# CORE.net
KiCad netlist of a schematic drawn in Altium Designer
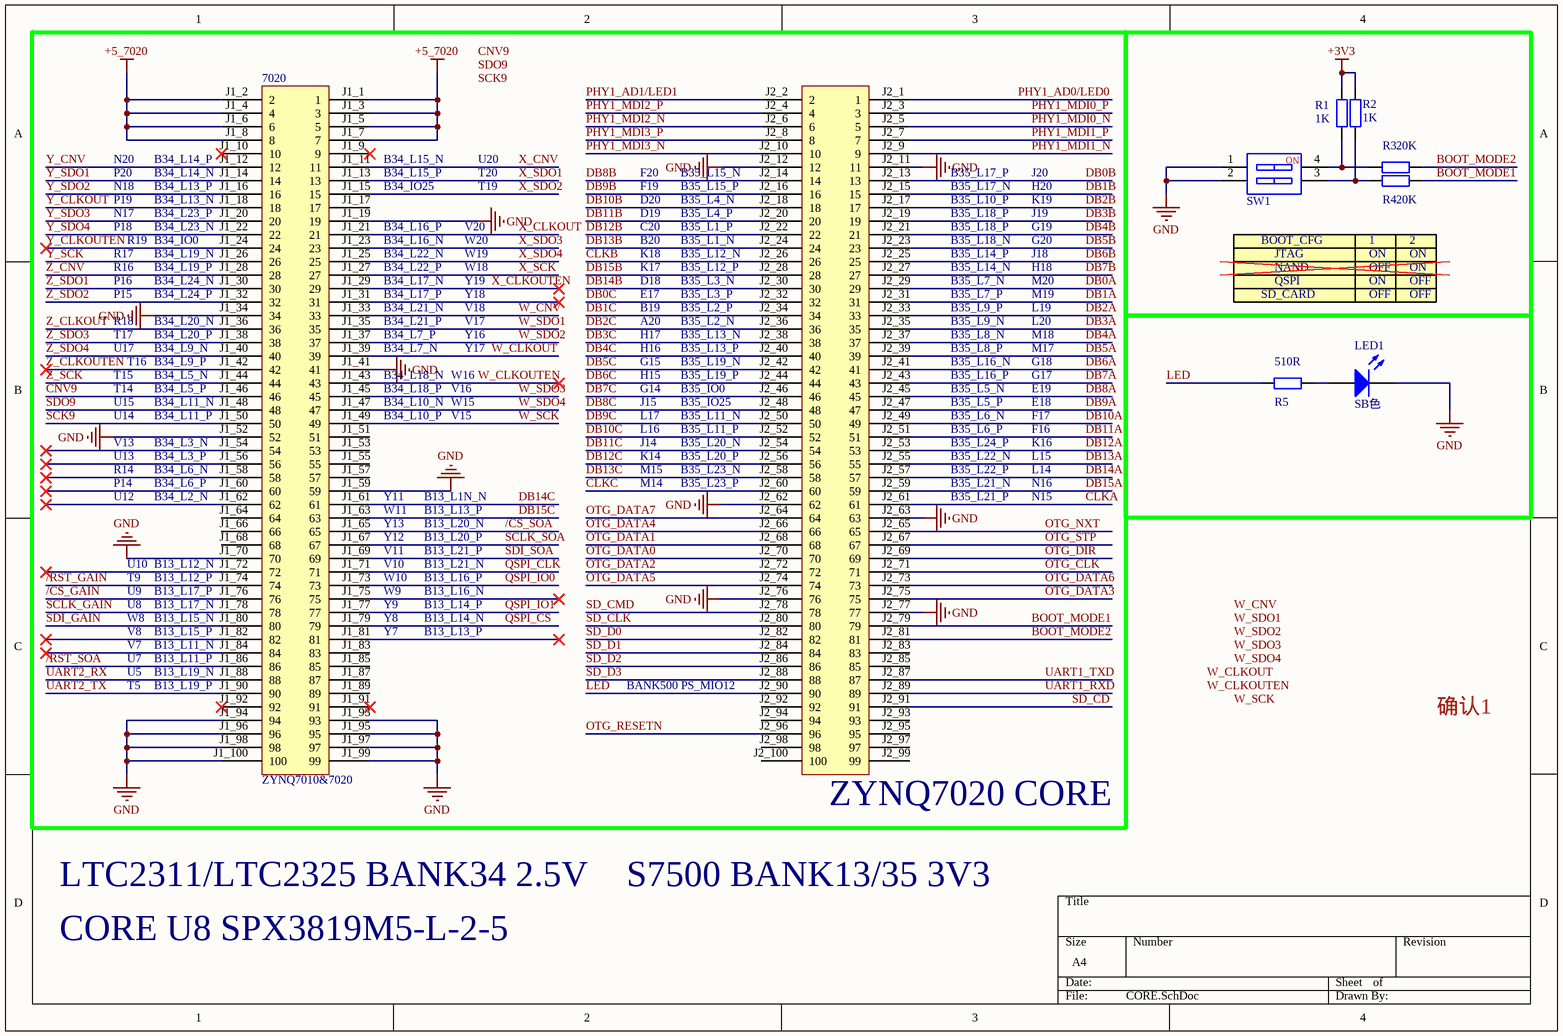
[diagram p0: CORE.SchDoc]

(export (version "E")
  (design (tool "Eeschema 10.0.6"))
  (components
    (comp (ref "7020")
      (value "ZYNQ7010&7020")
      (footprint "ZYNQ7010&7020_CB")
      (description "ZYNQ7010&7020 Core Board")
      (libsource (lib "领航者ZYNQ底板SCH&PCB封装库") (part "ZYNQ7010&7020"))
    )
    (comp (ref "LED1")
      (value "SB色")
      (footprint "LED0603_B")
      (description "贴片LED")
      (libsource (lib "0.3 - LED发光二极管-IR二极管_接收管-光耦") (part "LED"))
    )
    (comp (ref "R1")
      (value "1K")
      (footprint "R0402_L")
      (description "贴片电阻")
      (libsource (lib "0.1 - 电阻-电容-电感-保险丝-晶振-晶体-磁珠-电位器-法拉电容-馈通电容") (part "R"))
    )
    (comp (ref "R2")
      (value "1K")
      (footprint "R0402_L")
      (description "贴片电阻")
      (libsource (lib "0.1 - 电阻-电容-电感-保险丝-晶振-晶体-磁珠-电位器-法拉电容-馈通电容") (part "R"))
    )
    (comp (ref "R3")
      (value "20K")
      (footprint "R0402_L")
      (description "贴片电阻")
      (libsource (lib "0.1 - 电阻-电容-电感-保险丝-晶振-晶体-磁珠-电位器-法拉电容-馈通电容") (part "R"))
    )
    (comp (ref "R4")
      (value "20K")
      (footprint "R0402_L")
      (description "贴片电阻")
      (libsource (lib "0.1 - 电阻-电容-电感-保险丝-晶振-晶体-磁珠-电位器-法拉电容-馈通电容") (part "R"))
    )
    (comp (ref "R5")
      (value "510R")
      (footprint "R0603_L")
      (description "贴片电阻")
      (libsource (lib "0.1 - 电阻-电容-电感-保险丝-晶振-晶体-磁珠-电位器-法拉电容-馈通电容") (part "R"))
    )
    (comp (ref "SW1")
      (value "DIP-SW-2P")
      (footprint "SW DIP-2P")
      (description "2路拨码开关")
      (libsource (lib "0.5 - 按键_开关_蜂鸣器_电池_测试点_Mark点_铜柱") (part "DIP-SW-2P"))
    )
  )
  (nets
    (net (code "1") (name "+3V3") (class "Default")
      (node (ref "R1") (pin "2") (pinfunction "2_2") (pintype "passive"))
      (node (ref "R2") (pin "2") (pinfunction "2_2") (pintype "passive"))
    )
    (net (code "2") (name "+5_7020") (class "Default")
      (node (ref "7020") (pin "J1_1") (pinfunction "1_J1_1") (pintype "passive"))
      (node (ref "7020") (pin "J1_2") (pinfunction "2_J1_2") (pintype "passive"))
      (node (ref "7020") (pin "J1_3") (pinfunction "3_J1_3") (pintype "passive"))
      (node (ref "7020") (pin "J1_4") (pinfunction "4_J1_4") (pintype "passive"))
      (node (ref "7020") (pin "J1_5") (pinfunction "5_J1_5") (pintype "passive"))
      (node (ref "7020") (pin "J1_6") (pinfunction "6_J1_6") (pintype "passive"))
      (node (ref "7020") (pin "J1_7") (pinfunction "7_J1_7") (pintype "passive"))
      (node (ref "7020") (pin "J1_8") (pinfunction "8_J1_8") (pintype "passive"))
    )
    (net (code "3") (name "/BOOT_MODE1") (class "Default")
      (node (ref "7020") (pin "J2_79") (pinfunction "79_J2_79") (pintype "passive"))
      (node (ref "R4") (pin "2") (pinfunction "2_2") (pintype "passive"))
    )
    (net (code "4") (name "/BOOT_MODE2") (class "Default")
      (node (ref "7020") (pin "J2_81") (pinfunction "81_J2_81") (pintype "passive"))
      (node (ref "R3") (pin "2") (pinfunction "2_2") (pintype "passive"))
    )
    (net (code "5") (name "/CLKA") (class "Default")
      (node (ref "7020") (pin "J2_61") (pinfunction "61_J2_61") (pintype "passive"))
    )
    (net (code "6") (name "/CLKB") (class "Default")
      (node (ref "7020") (pin "J2_26") (pinfunction "26_J2_26") (pintype "passive"))
    )
    (net (code "7") (name "/CLKC") (class "Default")
      (node (ref "7020") (pin "J2_60") (pinfunction "60_J2_60") (pintype "passive"))
    )
    (net (code "8") (name "/CNV9") (class "Default")
      (node (ref "7020") (pin "J1_46") (pinfunction "46_J1_46") (pintype "passive"))
    )
    (net (code "9") (name "/DB0A") (class "Default")
      (node (ref "7020") (pin "J2_29") (pinfunction "29_J2_29") (pintype "passive"))
    )
    (net (code "10") (name "/DB0B") (class "Default")
      (node (ref "7020") (pin "J2_13") (pinfunction "13_J2_13") (pintype "passive"))
    )
    (net (code "11") (name "/DB0C") (class "Default")
      (node (ref "7020") (pin "J2_32") (pinfunction "32_J2_32") (pintype "passive"))
    )
    (net (code "12") (name "/DB1A") (class "Default")
      (node (ref "7020") (pin "J2_31") (pinfunction "31_J2_31") (pintype "passive"))
    )
    (net (code "13") (name "/DB1B") (class "Default")
      (node (ref "7020") (pin "J2_15") (pinfunction "15_J2_15") (pintype "passive"))
    )
    (net (code "14") (name "/DB1C") (class "Default")
      (node (ref "7020") (pin "J2_34") (pinfunction "34_J2_34") (pintype "passive"))
    )
    (net (code "15") (name "/DB2A") (class "Default")
      (node (ref "7020") (pin "J2_33") (pinfunction "33_J2_33") (pintype "passive"))
    )
    (net (code "16") (name "/DB2B") (class "Default")
      (node (ref "7020") (pin "J2_17") (pinfunction "17_J2_17") (pintype "passive"))
    )
    (net (code "17") (name "/DB2C") (class "Default")
      (node (ref "7020") (pin "J2_36") (pinfunction "36_J2_36") (pintype "passive"))
    )
    (net (code "18") (name "/DB3A") (class "Default")
      (node (ref "7020") (pin "J2_35") (pinfunction "35_J2_35") (pintype "passive"))
    )
    (net (code "19") (name "/DB3B") (class "Default")
      (node (ref "7020") (pin "J2_19") (pinfunction "19_J2_19") (pintype "passive"))
    )
    (net (code "20") (name "/DB3C") (class "Default")
      (node (ref "7020") (pin "J2_38") (pinfunction "38_J2_38") (pintype "passive"))
    )
    (net (code "21") (name "/DB4A") (class "Default")
      (node (ref "7020") (pin "J2_37") (pinfunction "37_J2_37") (pintype "passive"))
    )
    (net (code "22") (name "/DB4B") (class "Default")
      (node (ref "7020") (pin "J2_21") (pinfunction "21_J2_21") (pintype "passive"))
    )
    (net (code "23") (name "/DB4C") (class "Default")
      (node (ref "7020") (pin "J2_40") (pinfunction "40_J2_40") (pintype "passive"))
    )
    (net (code "24") (name "/DB5A") (class "Default")
      (node (ref "7020") (pin "J2_39") (pinfunction "39_J2_39") (pintype "passive"))
    )
    (net (code "25") (name "/DB5B") (class "Default")
      (node (ref "7020") (pin "J2_23") (pinfunction "23_J2_23") (pintype "passive"))
    )
    (net (code "26") (name "/DB5C") (class "Default")
      (node (ref "7020") (pin "J2_42") (pinfunction "42_J2_42") (pintype "passive"))
    )
    (net (code "27") (name "/DB6A") (class "Default")
      (node (ref "7020") (pin "J2_41") (pinfunction "41_J2_41") (pintype "passive"))
    )
    (net (code "28") (name "/DB6B") (class "Default")
      (node (ref "7020") (pin "J2_25") (pinfunction "25_J2_25") (pintype "passive"))
    )
    (net (code "29") (name "/DB6C") (class "Default")
      (node (ref "7020") (pin "J2_44") (pinfunction "44_J2_44") (pintype "passive"))
    )
    (net (code "30") (name "/DB7A") (class "Default")
      (node (ref "7020") (pin "J2_43") (pinfunction "43_J2_43") (pintype "passive"))
    )
    (net (code "31") (name "/DB7B") (class "Default")
      (node (ref "7020") (pin "J2_27") (pinfunction "27_J2_27") (pintype "passive"))
    )
    (net (code "32") (name "/DB7C") (class "Default")
      (node (ref "7020") (pin "J2_46") (pinfunction "46_J2_46") (pintype "passive"))
    )
    (net (code "33") (name "/DB8A") (class "Default")
      (node (ref "7020") (pin "J2_45") (pinfunction "45_J2_45") (pintype "passive"))
    )
    (net (code "34") (name "/DB8B") (class "Default")
      (node (ref "7020") (pin "J2_14") (pinfunction "14_J2_14") (pintype "passive"))
    )
    (net (code "35") (name "/DB8C") (class "Default")
      (node (ref "7020") (pin "J2_48") (pinfunction "48_J2_48") (pintype "passive"))
    )
    (net (code "36") (name "/DB9A") (class "Default")
      (node (ref "7020") (pin "J2_47") (pinfunction "47_J2_47") (pintype "passive"))
    )
    (net (code "37") (name "/DB9B") (class "Default")
      (node (ref "7020") (pin "J2_16") (pinfunction "16_J2_16") (pintype "passive"))
    )
    (net (code "38") (name "/DB9C") (class "Default")
      (node (ref "7020") (pin "J2_50") (pinfunction "50_J2_50") (pintype "passive"))
    )
    (net (code "39") (name "/DB10A") (class "Default")
      (node (ref "7020") (pin "J2_49") (pinfunction "49_J2_49") (pintype "passive"))
    )
    (net (code "40") (name "/DB10B") (class "Default")
      (node (ref "7020") (pin "J2_18") (pinfunction "18_J2_18") (pintype "passive"))
    )
    (net (code "41") (name "/DB10C") (class "Default")
      (node (ref "7020") (pin "J2_52") (pinfunction "52_J2_52") (pintype "passive"))
    )
    (net (code "42") (name "/DB11A") (class "Default")
      (node (ref "7020") (pin "J2_51") (pinfunction "51_J2_51") (pintype "passive"))
    )
    (net (code "43") (name "/DB11B") (class "Default")
      (node (ref "7020") (pin "J2_20") (pinfunction "20_J2_20") (pintype "passive"))
    )
    (net (code "44") (name "/DB11C") (class "Default")
      (node (ref "7020") (pin "J2_54") (pinfunction "54_J2_54") (pintype "passive"))
    )
    (net (code "45") (name "/DB12A") (class "Default")
      (node (ref "7020") (pin "J2_53") (pinfunction "53_J2_53") (pintype "passive"))
    )
    (net (code "46") (name "/DB12B") (class "Default")
      (node (ref "7020") (pin "J2_22") (pinfunction "22_J2_22") (pintype "passive"))
    )
    (net (code "47") (name "/DB12C") (class "Default")
      (node (ref "7020") (pin "J2_56") (pinfunction "56_J2_56") (pintype "passive"))
    )
    (net (code "48") (name "/DB13A") (class "Default")
      (node (ref "7020") (pin "J2_55") (pinfunction "55_J2_55") (pintype "passive"))
    )
    (net (code "49") (name "/DB13B") (class "Default")
      (node (ref "7020") (pin "J2_24") (pinfunction "24_J2_24") (pintype "passive"))
    )
    (net (code "50") (name "/DB13C") (class "Default")
      (node (ref "7020") (pin "J2_58") (pinfunction "58_J2_58") (pintype "passive"))
    )
    (net (code "51") (name "/DB14A") (class "Default")
      (node (ref "7020") (pin "J2_57") (pinfunction "57_J2_57") (pintype "passive"))
    )
    (net (code "52") (name "/DB14B") (class "Default")
      (node (ref "7020") (pin "J2_30") (pinfunction "30_J2_30") (pintype "passive"))
    )
    (net (code "53") (name "/DB14C") (class "Default")
      (node (ref "7020") (pin "J1_61") (pinfunction "61_J1_61") (pintype "passive"))
    )
    (net (code "54") (name "/DB15A") (class "Default")
      (node (ref "7020") (pin "J2_59") (pinfunction "59_J2_59") (pintype "passive"))
    )
    (net (code "55") (name "/DB15B") (class "Default")
      (node (ref "7020") (pin "J2_28") (pinfunction "28_J2_28") (pintype "passive"))
    )
    (net (code "56") (name "/DB15C") (class "Default")
      (node (ref "7020") (pin "J1_63") (pinfunction "63_J1_63") (pintype "passive"))
    )
    (net (code "57") (name "/LED") (class "Default")
      (node (ref "7020") (pin "J2_90") (pinfunction "90_J2_90") (pintype "passive"))
      (node (ref "R5") (pin "1") (pinfunction "1_1") (pintype "passive"))
    )
    (net (code "58") (name "/OTG_CLK") (class "Default")
      (node (ref "7020") (pin "J2_71") (pinfunction "71_J2_71") (pintype "passive"))
    )
    (net (code "59") (name "/OTG_DATA0") (class "Default")
      (node (ref "7020") (pin "J2_70") (pinfunction "70_J2_70") (pintype "passive"))
    )
    (net (code "60") (name "/OTG_DATA1") (class "Default")
      (node (ref "7020") (pin "J2_68") (pinfunction "68_J2_68") (pintype "passive"))
    )
    (net (code "61") (name "/OTG_DATA2") (class "Default")
      (node (ref "7020") (pin "J2_72") (pinfunction "72_J2_72") (pintype "passive"))
    )
    (net (code "62") (name "/OTG_DATA3") (class "Default")
      (node (ref "7020") (pin "J2_75") (pinfunction "75_J2_75") (pintype "passive"))
    )
    (net (code "63") (name "/OTG_DATA4") (class "Default")
      (node (ref "7020") (pin "J2_66") (pinfunction "66_J2_66") (pintype "passive"))
    )
    (net (code "64") (name "/OTG_DATA5") (class "Default")
      (node (ref "7020") (pin "J2_74") (pinfunction "74_J2_74") (pintype "passive"))
    )
    (net (code "65") (name "/OTG_DATA6") (class "Default")
      (node (ref "7020") (pin "J2_73") (pinfunction "73_J2_73") (pintype "passive"))
    )
    (net (code "66") (name "/OTG_DATA7") (class "Default")
      (node (ref "7020") (pin "J2_64") (pinfunction "64_J2_64") (pintype "passive"))
    )
    (net (code "67") (name "/OTG_DIR") (class "Default")
      (node (ref "7020") (pin "J2_69") (pinfunction "69_J2_69") (pintype "passive"))
    )
    (net (code "68") (name "/OTG_NXT") (class "Default")
      (node (ref "7020") (pin "J2_65") (pinfunction "65_J2_65") (pintype "passive"))
    )
    (net (code "69") (name "/OTG_RESETN") (class "Default")
      (node (ref "7020") (pin "J2_96") (pinfunction "96_J2_96") (pintype "passive"))
    )
    (net (code "70") (name "/OTG_STP") (class "Default")
      (node (ref "7020") (pin "J2_67") (pinfunction "67_J2_67") (pintype "passive"))
    )
    (net (code "71") (name "/PHY1_AD0{slash}LED0") (class "Default")
      (node (ref "7020") (pin "J2_1") (pinfunction "1_J2_1") (pintype "passive"))
    )
    (net (code "72") (name "/PHY1_AD1{slash}LED1") (class "Default")
      (node (ref "7020") (pin "J2_2") (pinfunction "2_J2_2") (pintype "passive"))
    )
    (net (code "73") (name "/PHY1_MDI0_N") (class "Default")
      (node (ref "7020") (pin "J2_5") (pinfunction "5_J2_5") (pintype "passive"))
    )
    (net (code "74") (name "/PHY1_MDI0_P") (class "Default")
      (node (ref "7020") (pin "J2_3") (pinfunction "3_J2_3") (pintype "passive"))
    )
    (net (code "75") (name "/PHY1_MDI1_N") (class "Default")
      (node (ref "7020") (pin "J2_9") (pinfunction "9_J2_9") (pintype "passive"))
    )
    (net (code "76") (name "/PHY1_MDI1_P") (class "Default")
      (node (ref "7020") (pin "J2_7") (pinfunction "7_J2_7") (pintype "passive"))
    )
    (net (code "77") (name "/PHY1_MDI2_N") (class "Default")
      (node (ref "7020") (pin "J2_6") (pinfunction "6_J2_6") (pintype "passive"))
    )
    (net (code "78") (name "/PHY1_MDI2_P") (class "Default")
      (node (ref "7020") (pin "J2_4") (pinfunction "4_J2_4") (pintype "passive"))
    )
    (net (code "79") (name "/PHY1_MDI3_N") (class "Default")
      (node (ref "7020") (pin "J2_10") (pinfunction "10_J2_10") (pintype "passive"))
    )
    (net (code "80") (name "/PHY1_MDI3_P") (class "Default")
      (node (ref "7020") (pin "J2_8") (pinfunction "8_J2_8") (pintype "passive"))
    )
    (net (code "81") (name "/QSPI_CLK") (class "Default")
      (node (ref "7020") (pin "J1_71") (pinfunction "71_J1_71") (pintype "passive"))
    )
    (net (code "82") (name "/QSPI_CS") (class "Default")
      (node (ref "7020") (pin "J1_79") (pinfunction "79_J1_79") (pintype "passive"))
    )
    (net (code "83") (name "/QSPI_IO0") (class "Default")
      (node (ref "7020") (pin "J1_73") (pinfunction "73_J1_73") (pintype "passive"))
    )
    (net (code "84") (name "/QSPI_IO1") (class "Default")
      (node (ref "7020") (pin "J1_77") (pinfunction "77_J1_77") (pintype "passive"))
    )
    (net (code "85") (name "/SCK9") (class "Default")
      (node (ref "7020") (pin "J1_50") (pinfunction "50_J1_50") (pintype "passive"))
    )
    (net (code "86") (name "/SCLK_GAIN") (class "Default")
      (node (ref "7020") (pin "J1_78") (pinfunction "78_J1_78") (pintype "passive"))
    )
    (net (code "87") (name "/SCLK_SOA") (class "Default")
      (node (ref "7020") (pin "J1_67") (pinfunction "67_J1_67") (pintype "passive"))
    )
    (net (code "88") (name "/SDI_GAIN") (class "Default")
      (node (ref "7020") (pin "J1_80") (pinfunction "80_J1_80") (pintype "passive"))
    )
    (net (code "89") (name "/SDI_SOA") (class "Default")
      (node (ref "7020") (pin "J1_69") (pinfunction "69_J1_69") (pintype "passive"))
    )
    (net (code "90") (name "/SDO9") (class "Default")
      (node (ref "7020") (pin "J1_48") (pinfunction "48_J1_48") (pintype "passive"))
    )
    (net (code "91") (name "/SD_CD") (class "Default")
      (node (ref "7020") (pin "J2_91") (pinfunction "91_J2_91") (pintype "passive"))
    )
    (net (code "92") (name "/SD_CLK") (class "Default")
      (node (ref "7020") (pin "J2_80") (pinfunction "80_J2_80") (pintype "passive"))
    )
    (net (code "93") (name "/SD_CMD") (class "Default")
      (node (ref "7020") (pin "J2_78") (pinfunction "78_J2_78") (pintype "passive"))
    )
    (net (code "94") (name "/SD_D0") (class "Default")
      (node (ref "7020") (pin "J2_82") (pinfunction "82_J2_82") (pintype "passive"))
    )
    (net (code "95") (name "/SD_D1") (class "Default")
      (node (ref "7020") (pin "J2_84") (pinfunction "84_J2_84") (pintype "passive"))
    )
    (net (code "96") (name "/SD_D2") (class "Default")
      (node (ref "7020") (pin "J2_86") (pinfunction "86_J2_86") (pintype "passive"))
    )
    (net (code "97") (name "/SD_D3") (class "Default")
      (node (ref "7020") (pin "J2_88") (pinfunction "88_J2_88") (pintype "passive"))
    )
    (net (code "98") (name "/UART1_RXD") (class "Default")
      (node (ref "7020") (pin "J2_89") (pinfunction "89_J2_89") (pintype "passive"))
    )
    (net (code "99") (name "/UART1_TXD") (class "Default")
      (node (ref "7020") (pin "J2_87") (pinfunction "87_J2_87") (pintype "passive"))
    )
    (net (code "100") (name "/UART2_RX") (class "Default")
      (node (ref "7020") (pin "J1_88") (pinfunction "88_J1_88") (pintype "passive"))
    )
    (net (code "101") (name "/UART2_TX") (class "Default")
      (node (ref "7020") (pin "J1_90") (pinfunction "90_J1_90") (pintype "passive"))
    )
    (net (code "102") (name "/W_CLKOUT") (class "Default")
      (node (ref "7020") (pin "J1_39") (pinfunction "39_J1_39") (pintype "passive"))
    )
    (net (code "103") (name "/W_CLKOUTEN") (class "Default")
      (node (ref "7020") (pin "J1_43") (pinfunction "43_J1_43") (pintype "passive+no_connect"))
    )
    (net (code "104") (name "/W_CNV") (class "Default")
      (node (ref "7020") (pin "J1_33") (pinfunction "33_J1_33") (pintype "passive"))
    )
    (net (code "105") (name "/W_SCK") (class "Default")
      (node (ref "7020") (pin "J1_49") (pinfunction "49_J1_49") (pintype "passive"))
    )
    (net (code "106") (name "/W_SDO1") (class "Default")
      (node (ref "7020") (pin "J1_35") (pinfunction "35_J1_35") (pintype "passive"))
    )
    (net (code "107") (name "/W_SDO2") (class "Default")
      (node (ref "7020") (pin "J1_37") (pinfunction "37_J1_37") (pintype "passive"))
    )
    (net (code "108") (name "/W_SDO3") (class "Default")
      (node (ref "7020") (pin "J1_45") (pinfunction "45_J1_45") (pintype "passive"))
    )
    (net (code "109") (name "/W_SDO4") (class "Default")
      (node (ref "7020") (pin "J1_47") (pinfunction "47_J1_47") (pintype "passive"))
    )
    (net (code "110") (name "/X_CLKOUT") (class "Default")
      (node (ref "7020") (pin "J1_21") (pinfunction "21_J1_21") (pintype "passive"))
    )
    (net (code "111") (name "/X_CLKOUTEN") (class "Default")
      (node (ref "7020") (pin "J1_29") (pinfunction "29_J1_29") (pintype "passive+no_connect"))
    )
    (net (code "112") (name "/X_CNV") (class "Default")
      (node (ref "7020") (pin "J1_11") (pinfunction "11_J1_11") (pintype "passive"))
    )
    (net (code "113") (name "/X_SCK") (class "Default")
      (node (ref "7020") (pin "J1_27") (pinfunction "27_J1_27") (pintype "passive"))
    )
    (net (code "114") (name "/X_SDO1") (class "Default")
      (node (ref "7020") (pin "J1_13") (pinfunction "13_J1_13") (pintype "passive"))
    )
    (net (code "115") (name "/X_SDO2") (class "Default")
      (node (ref "7020") (pin "J1_15") (pinfunction "15_J1_15") (pintype "passive"))
    )
    (net (code "116") (name "/X_SDO3") (class "Default")
      (node (ref "7020") (pin "J1_23") (pinfunction "23_J1_23") (pintype "passive"))
    )
    (net (code "117") (name "/X_SDO4") (class "Default")
      (node (ref "7020") (pin "J1_25") (pinfunction "25_J1_25") (pintype "passive"))
    )
    (net (code "118") (name "/Y_CLKOUT") (class "Default")
      (node (ref "7020") (pin "J1_18") (pinfunction "18_J1_18") (pintype "passive"))
    )
    (net (code "119") (name "/Y_CLKOUTEN") (class "Default")
      (node (ref "7020") (pin "J1_24") (pinfunction "24_J1_24") (pintype "passive+no_connect"))
    )
    (net (code "120") (name "/Y_CNV") (class "Default")
      (node (ref "7020") (pin "J1_12") (pinfunction "12_J1_12") (pintype "passive"))
    )
    (net (code "121") (name "/Y_SCK") (class "Default")
      (node (ref "7020") (pin "J1_26") (pinfunction "26_J1_26") (pintype "passive"))
    )
    (net (code "122") (name "/Y_SDO1") (class "Default")
      (node (ref "7020") (pin "J1_14") (pinfunction "14_J1_14") (pintype "passive"))
    )
    (net (code "123") (name "/Y_SDO2") (class "Default")
      (node (ref "7020") (pin "J1_16") (pinfunction "16_J1_16") (pintype "passive"))
    )
    (net (code "124") (name "/Y_SDO3") (class "Default")
      (node (ref "7020") (pin "J1_20") (pinfunction "20_J1_20") (pintype "passive"))
    )
    (net (code "125") (name "/Y_SDO4") (class "Default")
      (node (ref "7020") (pin "J1_22") (pinfunction "22_J1_22") (pintype "passive"))
    )
    (net (code "126") (name "/Z_CLKOUT") (class "Default")
      (node (ref "7020") (pin "J1_36") (pinfunction "36_J1_36") (pintype "passive"))
    )
    (net (code "127") (name "/Z_CLKOUTEN") (class "Default")
      (node (ref "7020") (pin "J1_42") (pinfunction "42_J1_42") (pintype "passive+no_connect"))
    )
    (net (code "128") (name "/Z_CNV") (class "Default")
      (node (ref "7020") (pin "J1_28") (pinfunction "28_J1_28") (pintype "passive"))
    )
    (net (code "129") (name "/Z_SCK") (class "Default")
      (node (ref "7020") (pin "J1_44") (pinfunction "44_J1_44") (pintype "passive"))
    )
    (net (code "130") (name "/Z_SDO1") (class "Default")
      (node (ref "7020") (pin "J1_30") (pinfunction "30_J1_30") (pintype "passive"))
    )
    (net (code "131") (name "/Z_SDO2") (class "Default")
      (node (ref "7020") (pin "J1_32") (pinfunction "32_J1_32") (pintype "passive"))
    )
    (net (code "132") (name "/Z_SDO3") (class "Default")
      (node (ref "7020") (pin "J1_38") (pinfunction "38_J1_38") (pintype "passive"))
    )
    (net (code "133") (name "/Z_SDO4") (class "Default")
      (node (ref "7020") (pin "J1_40") (pinfunction "40_J1_40") (pintype "passive"))
    )
    (net (code "134") (name "/{slash}CS_GAIN") (class "Default")
      (node (ref "7020") (pin "J1_76") (pinfunction "76_J1_76") (pintype "passive"))
    )
    (net (code "135") (name "/{slash}CS_SOA") (class "Default")
      (node (ref "7020") (pin "J1_65") (pinfunction "65_J1_65") (pintype "passive"))
    )
    (net (code "136") (name "/{slash}RST_GAIN") (class "Default")
      (node (ref "7020") (pin "J1_74") (pinfunction "74_J1_74") (pintype "passive"))
    )
    (net (code "137") (name "/{slash}RST_SOA") (class "Default")
      (node (ref "7020") (pin "J1_86") (pinfunction "86_J1_86") (pintype "passive"))
    )
    (net (code "138") (name "GND") (class "Default")
      (node (ref "7020") (pin "J1_100") (pinfunction "100_J1_100") (pintype "passive"))
      (node (ref "7020") (pin "J1_19") (pinfunction "19_J1_19") (pintype "passive"))
      (node (ref "7020") (pin "J1_34") (pinfunction "34_J1_34") (pintype "passive"))
      (node (ref "7020") (pin "J1_41") (pinfunction "41_J1_41") (pintype "passive"))
      (node (ref "7020") (pin "J1_52") (pinfunction "52_J1_52") (pintype "passive"))
      (node (ref "7020") (pin "J1_59") (pinfunction "59_J1_59") (pintype "passive"))
      (node (ref "7020") (pin "J1_70") (pinfunction "70_J1_70") (pintype "passive"))
      (node (ref "7020") (pin "J1_93") (pinfunction "93_J1_93") (pintype "passive"))
      (node (ref "7020") (pin "J1_94") (pinfunction "94_J1_94") (pintype "passive"))
      (node (ref "7020") (pin "J1_95") (pinfunction "95_J1_95") (pintype "passive"))
      (node (ref "7020") (pin "J1_96") (pinfunction "96_J1_96") (pintype "passive"))
      (node (ref "7020") (pin "J1_97") (pinfunction "97_J1_97") (pintype "passive"))
      (node (ref "7020") (pin "J1_98") (pinfunction "98_J1_98") (pintype "passive"))
      (node (ref "7020") (pin "J1_99") (pinfunction "99_J1_99") (pintype "passive"))
      (node (ref "7020") (pin "J2_11") (pinfunction "11_J2_11") (pintype "passive"))
      (node (ref "7020") (pin "J2_12") (pinfunction "12_J2_12") (pintype "passive"))
      (node (ref "7020") (pin "J2_62") (pinfunction "62_J2_62") (pintype "passive"))
      (node (ref "7020") (pin "J2_63") (pinfunction "63_J2_63") (pintype "passive"))
      (node (ref "7020") (pin "J2_76") (pinfunction "76_J2_76") (pintype "passive"))
      (node (ref "7020") (pin "J2_77") (pinfunction "77_J2_77") (pintype "passive"))
      (node (ref "LED1") (pin "2") (pinfunction "K_2") (pintype "passive"))
      (node (ref "SW1") (pin "1") (pinfunction "1_1") (pintype "passive"))
      (node (ref "SW1") (pin "2") (pinfunction "2_2") (pintype "passive"))
    )
    (net (code "139") (name "Net-(LED1-A)") (class "Default")
      (node (ref "LED1") (pin "1") (pinfunction "A_1") (pintype "passive"))
      (node (ref "R5") (pin "2") (pinfunction "2_2") (pintype "passive"))
    )
    (net (code "140") (name "Net-(R1-Pad1)") (class "Default")
      (node (ref "R1") (pin "1") (pinfunction "1_1") (pintype "passive"))
      (node (ref "R3") (pin "1") (pinfunction "1_1") (pintype "passive"))
      (node (ref "SW1") (pin "4") (pinfunction "4_4") (pintype "passive"))
    )
    (net (code "141") (name "Net-(R2-Pad1)") (class "Default")
      (node (ref "R2") (pin "1") (pinfunction "1_1") (pintype "passive"))
      (node (ref "R4") (pin "1") (pinfunction "1_1") (pintype "passive"))
      (node (ref "SW1") (pin "3") (pinfunction "3_3") (pintype "passive"))
    )
    (net (code "142") (name "unconnected-(7020-9-PadJ1_9)") (class "Default")
      (node (ref "7020") (pin "J1_9") (pinfunction "9_J1_9") (pintype "passive+no_connect"))
    )
    (net (code "143") (name "unconnected-(7020-10-PadJ1_10)") (class "Default")
      (node (ref "7020") (pin "J1_10") (pinfunction "10_J1_10") (pintype "passive+no_connect"))
    )
    (net (code "144") (name "unconnected-(7020-17-PadJ1_17)") (class "Default")
      (node (ref "7020") (pin "J1_17") (pinfunction "17_J1_17") (pintype "passive"))
    )
    (net (code "145") (name "unconnected-(7020-31-PadJ1_31)") (class "Default")
      (node (ref "7020") (pin "J1_31") (pinfunction "31_J1_31") (pintype "passive+no_connect"))
    )
    (net (code "146") (name "unconnected-(7020-51-PadJ1_51)") (class "Default")
      (node (ref "7020") (pin "J1_51") (pinfunction "51_J1_51") (pintype "passive"))
    )
    (net (code "147") (name "unconnected-(7020-53-PadJ1_53)") (class "Default")
      (node (ref "7020") (pin "J1_53") (pinfunction "53_J1_53") (pintype "passive"))
    )
    (net (code "148") (name "unconnected-(7020-54-PadJ1_54)") (class "Default")
      (node (ref "7020") (pin "J1_54") (pinfunction "54_J1_54") (pintype "passive+no_connect"))
    )
    (net (code "149") (name "unconnected-(7020-55-PadJ1_55)") (class "Default")
      (node (ref "7020") (pin "J1_55") (pinfunction "55_J1_55") (pintype "passive"))
    )
    (net (code "150") (name "unconnected-(7020-56-PadJ1_56)") (class "Default")
      (node (ref "7020") (pin "J1_56") (pinfunction "56_J1_56") (pintype "passive+no_connect"))
    )
    (net (code "151") (name "unconnected-(7020-57-PadJ1_57)") (class "Default")
      (node (ref "7020") (pin "J1_57") (pinfunction "57_J1_57") (pintype "passive"))
    )
    (net (code "152") (name "unconnected-(7020-58-PadJ1_58)") (class "Default")
      (node (ref "7020") (pin "J1_58") (pinfunction "58_J1_58") (pintype "passive+no_connect"))
    )
    (net (code "153") (name "unconnected-(7020-60-PadJ1_60)") (class "Default")
      (node (ref "7020") (pin "J1_60") (pinfunction "60_J1_60") (pintype "passive+no_connect"))
    )
    (net (code "154") (name "unconnected-(7020-62-PadJ1_62)") (class "Default")
      (node (ref "7020") (pin "J1_62") (pinfunction "62_J1_62") (pintype "passive+no_connect"))
    )
    (net (code "155") (name "unconnected-(7020-64-PadJ1_64)") (class "Default")
      (node (ref "7020") (pin "J1_64") (pinfunction "64_J1_64") (pintype "passive"))
    )
    (net (code "156") (name "unconnected-(7020-66-PadJ1_66)") (class "Default")
      (node (ref "7020") (pin "J1_66") (pinfunction "66_J1_66") (pintype "passive"))
    )
    (net (code "157") (name "unconnected-(7020-68-PadJ1_68)") (class "Default")
      (node (ref "7020") (pin "J1_68") (pinfunction "68_J1_68") (pintype "passive"))
    )
    (net (code "158") (name "unconnected-(7020-72-PadJ1_72)") (class "Default")
      (node (ref "7020") (pin "J1_72") (pinfunction "72_J1_72") (pintype "passive+no_connect"))
    )
    (net (code "159") (name "unconnected-(7020-75-PadJ1_75)") (class "Default")
      (node (ref "7020") (pin "J1_75") (pinfunction "75_J1_75") (pintype "passive+no_connect"))
    )
    (net (code "160") (name "unconnected-(7020-81-PadJ1_81)") (class "Default")
      (node (ref "7020") (pin "J1_81") (pinfunction "81_J1_81") (pintype "passive+no_connect"))
    )
    (net (code "161") (name "unconnected-(7020-82-PadJ1_82)") (class "Default")
      (node (ref "7020") (pin "J1_82") (pinfunction "82_J1_82") (pintype "passive+no_connect"))
    )
    (net (code "162") (name "unconnected-(7020-83-PadJ1_83)") (class "Default")
      (node (ref "7020") (pin "J1_83") (pinfunction "83_J1_83") (pintype "passive"))
    )
    (net (code "163") (name "unconnected-(7020-83-PadJ2_83)") (class "Default")
      (node (ref "7020") (pin "J2_83") (pinfunction "83_J2_83") (pintype "passive"))
    )
    (net (code "164") (name "unconnected-(7020-84-PadJ1_84)") (class "Default")
      (node (ref "7020") (pin "J1_84") (pinfunction "84_J1_84") (pintype "passive+no_connect"))
    )
    (net (code "165") (name "unconnected-(7020-85-PadJ1_85)") (class "Default")
      (node (ref "7020") (pin "J1_85") (pinfunction "85_J1_85") (pintype "passive"))
    )
    (net (code "166") (name "unconnected-(7020-85-PadJ2_85)") (class "Default")
      (node (ref "7020") (pin "J2_85") (pinfunction "85_J2_85") (pintype "passive"))
    )
    (net (code "167") (name "unconnected-(7020-87-PadJ1_87)") (class "Default")
      (node (ref "7020") (pin "J1_87") (pinfunction "87_J1_87") (pintype "passive"))
    )
    (net (code "168") (name "unconnected-(7020-89-PadJ1_89)") (class "Default")
      (node (ref "7020") (pin "J1_89") (pinfunction "89_J1_89") (pintype "passive"))
    )
    (net (code "169") (name "unconnected-(7020-91-PadJ1_91)") (class "Default")
      (node (ref "7020") (pin "J1_91") (pinfunction "91_J1_91") (pintype "passive+no_connect"))
    )
    (net (code "170") (name "unconnected-(7020-92-PadJ1_92)") (class "Default")
      (node (ref "7020") (pin "J1_92") (pinfunction "92_J1_92") (pintype "passive+no_connect"))
    )
    (net (code "171") (name "unconnected-(7020-92-PadJ2_92)") (class "Default")
      (node (ref "7020") (pin "J2_92") (pinfunction "92_J2_92") (pintype "passive"))
    )
    (net (code "172") (name "unconnected-(7020-93-PadJ2_93)") (class "Default")
      (node (ref "7020") (pin "J2_93") (pinfunction "93_J2_93") (pintype "passive"))
    )
    (net (code "173") (name "unconnected-(7020-94-PadJ2_94)") (class "Default")
      (node (ref "7020") (pin "J2_94") (pinfunction "94_J2_94") (pintype "passive"))
    )
    (net (code "174") (name "unconnected-(7020-95-PadJ2_95)") (class "Default")
      (node (ref "7020") (pin "J2_95") (pinfunction "95_J2_95") (pintype "passive"))
    )
    (net (code "175") (name "unconnected-(7020-97-PadJ2_97)") (class "Default")
      (node (ref "7020") (pin "J2_97") (pinfunction "97_J2_97") (pintype "passive"))
    )
    (net (code "176") (name "unconnected-(7020-98-PadJ2_98)") (class "Default")
      (node (ref "7020") (pin "J2_98") (pinfunction "98_J2_98") (pintype "passive"))
    )
    (net (code "177") (name "unconnected-(7020-99-PadJ2_99)") (class "Default")
      (node (ref "7020") (pin "J2_99") (pinfunction "99_J2_99") (pintype "passive"))
    )
    (net (code "178") (name "unconnected-(7020-100-PadJ2_100)") (class "Default")
      (node (ref "7020") (pin "J2_100") (pinfunction "100_J2_100") (pintype "passive"))
    )
  )
)
